# MING_RTD.net
KiCad netlist of a schematic drawn in Altium Designer
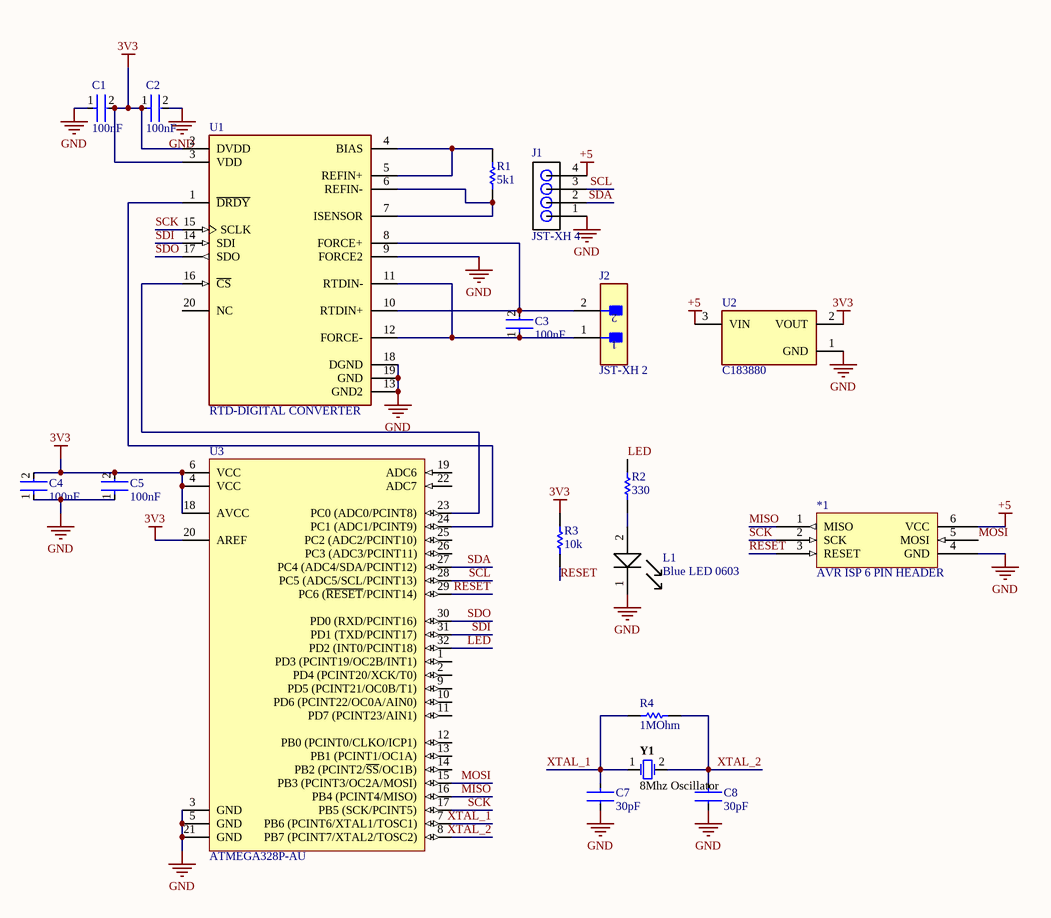
[diagram p0: MING RTD.SchDoc]

(export (version "E")
  (design (tool "Eeschema 10.0.6"))
  (components
    (comp (ref "*1")
      (value "AVR ISP 6 PIN HEADER")
      (footprint "AVR ISP 6 PIN HEADER")
      (libsource (lib "Main") (part "AVR ISP 6 PIN HEADER"))
    )
    (comp (ref "C1")
      (value "100nF")
      (footprint "FP-GCM188-0_1-IPC_C")
      (fields (field (name "TOLERANCE") "10%"))
      (libsource (lib "Main") (part "C307331"))
    )
    (comp (ref "C2")
      (value "100nF")
      (footprint "FP-GCM188-0_1-IPC_C")
      (fields (field (name "TOLERANCE") "10%"))
      (libsource (lib "Main") (part "C307331"))
    )
    (comp (ref "C3")
      (value "100nF")
      (footprint "FP-GCM188-0_1-IPC_C")
      (fields (field (name "TOLERANCE") "10%"))
      (libsource (lib "Main") (part "C307331"))
    )
    (comp (ref "C4")
      (value "100nF")
      (footprint "FP-GCM188-0_1-IPC_C")
      (fields (field (name "TOLERANCE") "10%"))
      (libsource (lib "Main") (part "C307331"))
    )
    (comp (ref "C5")
      (value "100nF")
      (footprint "FP-GCM188-0_1-IPC_C")
      (fields (field (name "TOLERANCE") "10%"))
      (libsource (lib "Main") (part "C307331"))
    )
    (comp (ref "C7") (value "30pF") (footprint "CAPC1005X06L") (libsource (lib "Main") (part "C1570")))
    (comp (ref "C8") (value "30pF") (footprint "CAPC1005X06L") (libsource (lib "Main") (part "C1570")))
    (comp (ref "J1") (value "JST-XH 4") (footprint "C146120") (libsource (lib "Main") (part "C146120")))
    (comp (ref "J2")
      (value "JST-XH 2")
      (footprint "FP-B2B-XH-A_LF_SN-MFG")
      (description "CONN HEADER VERT 2POS 2.5MM")
      (libsource (lib "Main") (part "C20079"))
    )
    (comp (ref "L1")
      (value "Blue LED 0603")
      (footprint "C165977")
      (description "Blue 465~475nm 0603 Light Emitting Diodes (LED) ROHS")
      (libsource (lib "Main") (part "C72041"))
    )
    (comp (ref "R1")
      (value "5k1")
      (footprint "RESC1608X06L")
      (fields (field (name "PART NUMBER") "ERJ-3EKF5101V") (field (name "MANUFACTURER") "Panasonic"))
      (libsource (lib "Main") (part "C23186"))
    )
    (comp (ref "R2")
      (value "330")
      (footprint "RESC1608X06L")
      (fields (field (name "MANUFACTURER") "Panasonic") (field (name "PART NUMBER") "ERJ1GNF1004C"))
      (libsource (lib "Main") (part "C23138"))
    )
    (comp (ref "R3")
      (value "10k")
      (footprint "RESC1608X06L")
      (fields (field (name "PART NUMBER") "ERJ-3EKF5101V") (field (name "MANUFACTURER") "Panasonic"))
      (libsource (lib "Main") (part "C25804"))
    )
    (comp (ref "R4")
      (value "1MOhm")
      (footprint "RESC1608X06L")
      (fields (field (name "MANUFACTURER") "Panasonic") (field (name "PART NUMBER") "ERJ1GNF1004C"))
      (libsource (lib "Main") (part "C22935"))
    )
    (comp (ref "U1")
      (value "RTD-DIGITAL CONVERTER")
      (footprint "FP-A20-1-IPC_C")
      (description "IC RTD TO DIGITAL CONVERT 20SSOP")
      (libsource (lib "Main") (part "C779509"))
    )
    (comp (ref "U2")
      (value "C183880")
      (footprint "FP-SOT23-IPC_C")
      (description "6V - - - Fixed 3.3V SOT-23-3L Linear Voltage Regulators (LDO) ROHS")
      (fields
        (field (name "MANUFACTURER PART NUMBER") "AP2120N-3.3TRG1")
        (field (name "MANUFACTURER") "Diodes Inc.")
      )
      (libsource (lib "Main") (part "LN1121P332MR-G"))
    )
    (comp (ref "U3") (value "ATMEGA328P-AU") (footprint "32A_L") (libsource (lib "Main") (part "C14877")))
    (comp (ref "Y1")
      (value "8Mhz Oscillator")
      (footprint "C115962")
      (description "Resistance Weld Crystal, 8 MHz, +/- 30 ppm, -20 to 70 degC, 2-Pin SMD, RoHS, Tape and Reel")
      (fields (field (name "MANUFACTURER") "FOX Electronics") (field (name "TOLERANCE") "50ppm"))
      (libsource (lib "Main") (part "C115962"))
    )
  )
  (nets
    (net (code "1") (name "+5") (class "Default")
      (node (ref "*1") (pin "6") (pinfunction "VCC_6") (pintype "power_in"))
      (node (ref "J1") (pin "4") (pinfunction "4_4") (pintype "passive"))
      (node (ref "U2") (pin "3") (pinfunction "VIN_3") (pintype "power_in"))
    )
    (net (code "2") (name "/LED") (class "Default")
      (node (ref "R2") (pin "2") (pinfunction "2_2") (pintype "passive"))
      (node (ref "U3") (pin "32") (pinfunction "PD2_(INT0/PCINT18)_32") (pintype "bidirectional"))
    )
    (net (code "3") (name "/MISO") (class "Default")
      (node (ref "*1") (pin "1") (pinfunction "MISO_1") (pintype "output"))
      (node (ref "U3") (pin "16") (pinfunction "PB4_(PCINT4/MISO)_16") (pintype "bidirectional"))
    )
    (net (code "4") (name "/MOSI") (class "Default")
      (node (ref "*1") (pin "5") (pinfunction "MOSI_5") (pintype "input"))
      (node (ref "U3") (pin "15") (pinfunction "PB3_(PCINT3/OC2A/MOSI)_15") (pintype "bidirectional"))
    )
    (net (code "5") (name "/RESET") (class "Default")
      (node (ref "*1") (pin "3") (pinfunction "RESET_3") (pintype "input"))
      (node (ref "R3") (pin "1") (pinfunction "1_1") (pintype "passive"))
      (node (ref "U3") (pin "29") (pinfunction "PC6_(~{RESET}/PCINT14)_29") (pintype "bidirectional"))
    )
    (net (code "6") (name "/SCK") (class "Default")
      (node (ref "*1") (pin "2") (pinfunction "SCK_2") (pintype "input"))
      (node (ref "U1") (pin "15") (pinfunction "SCLK_15") (pintype "input"))
      (node (ref "U3") (pin "17") (pinfunction "PB5_(SCK/PCINT5)_17") (pintype "bidirectional"))
    )
    (net (code "7") (name "/SCL") (class "Default")
      (node (ref "J1") (pin "3") (pinfunction "3_3") (pintype "passive"))
      (node (ref "U3") (pin "28") (pinfunction "PC5_(ADC5/SCL/PCINT13)_28") (pintype "bidirectional"))
    )
    (net (code "8") (name "/SDA") (class "Default")
      (node (ref "J1") (pin "2") (pinfunction "2_2") (pintype "passive"))
      (node (ref "U3") (pin "27") (pinfunction "PC4_(ADC4/SDA/PCINT12)_27") (pintype "bidirectional"))
    )
    (net (code "9") (name "/SDI") (class "Default")
      (node (ref "U1") (pin "14") (pinfunction "SDI_14") (pintype "input"))
      (node (ref "U3") (pin "31") (pinfunction "PD1_(TXD/PCINT17)_31") (pintype "bidirectional"))
    )
    (net (code "10") (name "/SDO") (class "Default")
      (node (ref "U1") (pin "17") (pinfunction "SDO_17") (pintype "output"))
      (node (ref "U3") (pin "30") (pinfunction "PD0_(RXD/PCINT16)_30") (pintype "bidirectional"))
    )
    (net (code "11") (name "/XTAL_1") (class "Default")
      (node (ref "C7") (pin "1") (pinfunction "1_1") (pintype "passive"))
      (node (ref "R4") (pin "1") (pinfunction "1_1") (pintype "passive"))
      (node (ref "U3") (pin "7") (pinfunction "PB6_(PCINT6/XTAL1/TOSC1)_7") (pintype "bidirectional"))
      (node (ref "Y1") (pin "1") (pinfunction "1_1") (pintype "passive"))
    )
    (net (code "12") (name "/XTAL_2") (class "Default")
      (node (ref "C8") (pin "1") (pinfunction "1_1") (pintype "passive"))
      (node (ref "R4") (pin "2") (pinfunction "2_2") (pintype "passive"))
      (node (ref "U3") (pin "8") (pinfunction "PB7_(PCINT7/XTAL2/TOSC2)_8") (pintype "bidirectional"))
      (node (ref "Y1") (pin "2") (pinfunction "2_2") (pintype "passive"))
    )
    (net (code "13") (name "3V3") (class "Default")
      (node (ref "C1") (pin "2") (pinfunction "2_2") (pintype "passive"))
      (node (ref "C2") (pin "1") (pinfunction "1_1") (pintype "passive"))
      (node (ref "C4") (pin "2") (pinfunction "2_2") (pintype "passive"))
      (node (ref "C5") (pin "2") (pinfunction "2_2") (pintype "passive"))
      (node (ref "R3") (pin "2") (pinfunction "2_2") (pintype "passive"))
      (node (ref "U1") (pin "2") (pinfunction "DVDD_2") (pintype "power_in"))
      (node (ref "U1") (pin "3") (pinfunction "VDD_3") (pintype "power_in"))
      (node (ref "U2") (pin "2") (pinfunction "VOUT_2") (pintype "power_in"))
      (node (ref "U3") (pin "18") (pinfunction "AVCC_18") (pintype "power_in"))
      (node (ref "U3") (pin "20") (pinfunction "AREF_20") (pintype "passive"))
      (node (ref "U3") (pin "4") (pinfunction "VCC_4") (pintype "power_in"))
      (node (ref "U3") (pin "6") (pinfunction "VCC_6") (pintype "power_in"))
    )
    (net (code "14") (name "GND") (class "Default")
      (node (ref "*1") (pin "4") (pinfunction "GND_4") (pintype "power_in"))
      (node (ref "C1") (pin "1") (pinfunction "1_1") (pintype "passive"))
      (node (ref "C2") (pin "2") (pinfunction "2_2") (pintype "passive"))
      (node (ref "C4") (pin "1") (pinfunction "1_1") (pintype "passive"))
      (node (ref "C5") (pin "1") (pinfunction "1_1") (pintype "passive"))
      (node (ref "C7") (pin "2") (pinfunction "2_2") (pintype "passive"))
      (node (ref "C8") (pin "2") (pinfunction "2_2") (pintype "passive"))
      (node (ref "J1") (pin "1") (pinfunction "1_1") (pintype "passive"))
      (node (ref "L1") (pin "1") (pinfunction "3_1") (pintype "passive"))
      (node (ref "U1") (pin "13") (pinfunction "GND2_13") (pintype "power_in"))
      (node (ref "U1") (pin "18") (pinfunction "DGND_18") (pintype "power_in"))
      (node (ref "U1") (pin "19") (pinfunction "GND_19") (pintype "power_in"))
      (node (ref "U1") (pin "9") (pinfunction "FORCE2_9") (pintype "passive"))
      (node (ref "U2") (pin "1") (pinfunction "GND_1") (pintype "power_in"))
      (node (ref "U3") (pin "21") (pinfunction "GND_21") (pintype "power_in"))
      (node (ref "U3") (pin "3") (pinfunction "GND_3") (pintype "power_in"))
      (node (ref "U3") (pin "5") (pinfunction "GND_5") (pintype "power_in"))
    )
    (net (code "15") (name "Net-(L1-Pad2)") (class "Default")
      (node (ref "L1") (pin "2") (pinfunction "2_2") (pintype "passive"))
      (node (ref "R2") (pin "1") (pinfunction "1_1") (pintype "passive"))
    )
    (net (code "16") (name "Net-(U1-BIAS)") (class "Default")
      (node (ref "R1") (pin "2") (pinfunction "2_2") (pintype "passive"))
      (node (ref "U1") (pin "4") (pinfunction "BIAS_4") (pintype "passive"))
      (node (ref "U1") (pin "5") (pinfunction "REFIN+_5") (pintype "passive"))
    )
    (net (code "17") (name "Net-(U1-FORCE+)") (class "Default")
      (node (ref "C3") (pin "2") (pinfunction "2_2") (pintype "passive"))
      (node (ref "J2") (pin "2") (pinfunction "2_2") (pintype "passive"))
      (node (ref "U1") (pin "10") (pinfunction "RTDIN+_10") (pintype "passive"))
      (node (ref "U1") (pin "8") (pinfunction "FORCE+_8") (pintype "passive"))
    )
    (net (code "18") (name "Net-(U1-FORCE-)") (class "Default")
      (node (ref "C3") (pin "1") (pinfunction "1_1") (pintype "passive"))
      (node (ref "J2") (pin "1") (pinfunction "1_1") (pintype "passive"))
      (node (ref "U1") (pin "11") (pinfunction "RTDIN-_11") (pintype "passive"))
      (node (ref "U1") (pin "12") (pinfunction "FORCE-_12") (pintype "passive"))
    )
    (net (code "19") (name "Net-(U1-ISENSOR)") (class "Default")
      (node (ref "R1") (pin "1") (pinfunction "1_1") (pintype "passive"))
      (node (ref "U1") (pin "6") (pinfunction "REFIN-_6") (pintype "passive"))
      (node (ref "U1") (pin "7") (pinfunction "ISENSOR_7") (pintype "passive"))
    )
    (net (code "20") (name "Net-(U1-~{CS})") (class "Default")
      (node (ref "U1") (pin "16") (pinfunction "~{CS}_16") (pintype "input"))
      (node (ref "U3") (pin "23") (pinfunction "PC0_(ADC0/PCINT8)_23") (pintype "bidirectional"))
    )
    (net (code "21") (name "Net-(U1-~{DRDY})") (class "Default")
      (node (ref "U1") (pin "1") (pinfunction "~{DRDY}_1") (pintype "passive"))
      (node (ref "U3") (pin "24") (pinfunction "PC1_(ADC1/PCINT9)_24") (pintype "bidirectional"))
    )
    (net (code "22") (name "unconnected-(U1-NC-Pad20)") (class "Default")
      (node (ref "U1") (pin "20") (pinfunction "NC_20") (pintype "passive"))
    )
    (net (code "23") (name "unconnected-(U3-ADC6-Pad19)") (class "Default")
      (node (ref "U3") (pin "19") (pinfunction "ADC6_19") (pintype "input"))
    )
    (net (code "24") (name "unconnected-(U3-ADC7-Pad22)") (class "Default")
      (node (ref "U3") (pin "22") (pinfunction "ADC7_22") (pintype "input"))
    )
    (net (code "25") (name "unconnected-(U3-PB0_(PCINT0{slash}CLKO{slash}ICP1)-Pad12)") (class "Default")
      (node (ref "U3") (pin "12") (pinfunction "PB0_(PCINT0/CLKO/ICP1)_12") (pintype "bidirectional"))
    )
    (net (code "26") (name "unconnected-(U3-PB1_(PCINT1{slash}OC1A)-Pad13)") (class "Default")
      (node (ref "U3") (pin "13") (pinfunction "PB1_(PCINT1/OC1A)_13") (pintype "bidirectional"))
    )
    (net (code "27") (name "unconnected-(U3-PB2_(PCINT2{slash}~{SS}{slash}OC1B)-Pad14)") (class "Default")
      (node (ref "U3") (pin "14") (pinfunction "PB2_(PCINT2/~{SS}/OC1B)_14") (pintype "bidirectional"))
    )
    (net (code "28") (name "unconnected-(U3-PC2_(ADC2{slash}PCINT10)-Pad25)") (class "Default")
      (node (ref "U3") (pin "25") (pinfunction "PC2_(ADC2/PCINT10)_25") (pintype "bidirectional"))
    )
    (net (code "29") (name "unconnected-(U3-PC3_(ADC3{slash}PCINT11)-Pad26)") (class "Default")
      (node (ref "U3") (pin "26") (pinfunction "PC3_(ADC3/PCINT11)_26") (pintype "bidirectional"))
    )
    (net (code "30") (name "unconnected-(U3-PD3_(PCINT19{slash}OC2B{slash}INT1)-Pad1)") (class "Default")
      (node (ref "U3") (pin "1") (pinfunction "PD3_(PCINT19/OC2B/INT1)_1") (pintype "bidirectional"))
    )
    (net (code "31") (name "unconnected-(U3-PD4_(PCINT20{slash}XCK{slash}T0)-Pad2)") (class "Default")
      (node (ref "U3") (pin "2") (pinfunction "PD4_(PCINT20/XCK/T0)_2") (pintype "bidirectional"))
    )
    (net (code "32") (name "unconnected-(U3-PD5_(PCINT21{slash}OC0B{slash}T1)-Pad9)") (class "Default")
      (node (ref "U3") (pin "9") (pinfunction "PD5_(PCINT21/OC0B/T1)_9") (pintype "bidirectional"))
    )
    (net (code "33") (name "unconnected-(U3-PD6_(PCINT22{slash}OC0A{slash}AIN0)-Pad10)") (class "Default")
      (node (ref "U3") (pin "10") (pinfunction "PD6_(PCINT22/OC0A/AIN0)_10") (pintype "bidirectional"))
    )
    (net (code "34") (name "unconnected-(U3-PD7_(PCINT23{slash}AIN1)-Pad11)") (class "Default")
      (node (ref "U3") (pin "11") (pinfunction "PD7_(PCINT23/AIN1)_11") (pintype "bidirectional"))
    )
  )
)
